# ESP32_Expanded_Board.net
KiCad netlist of a schematic drawn in EasyEDA Pro
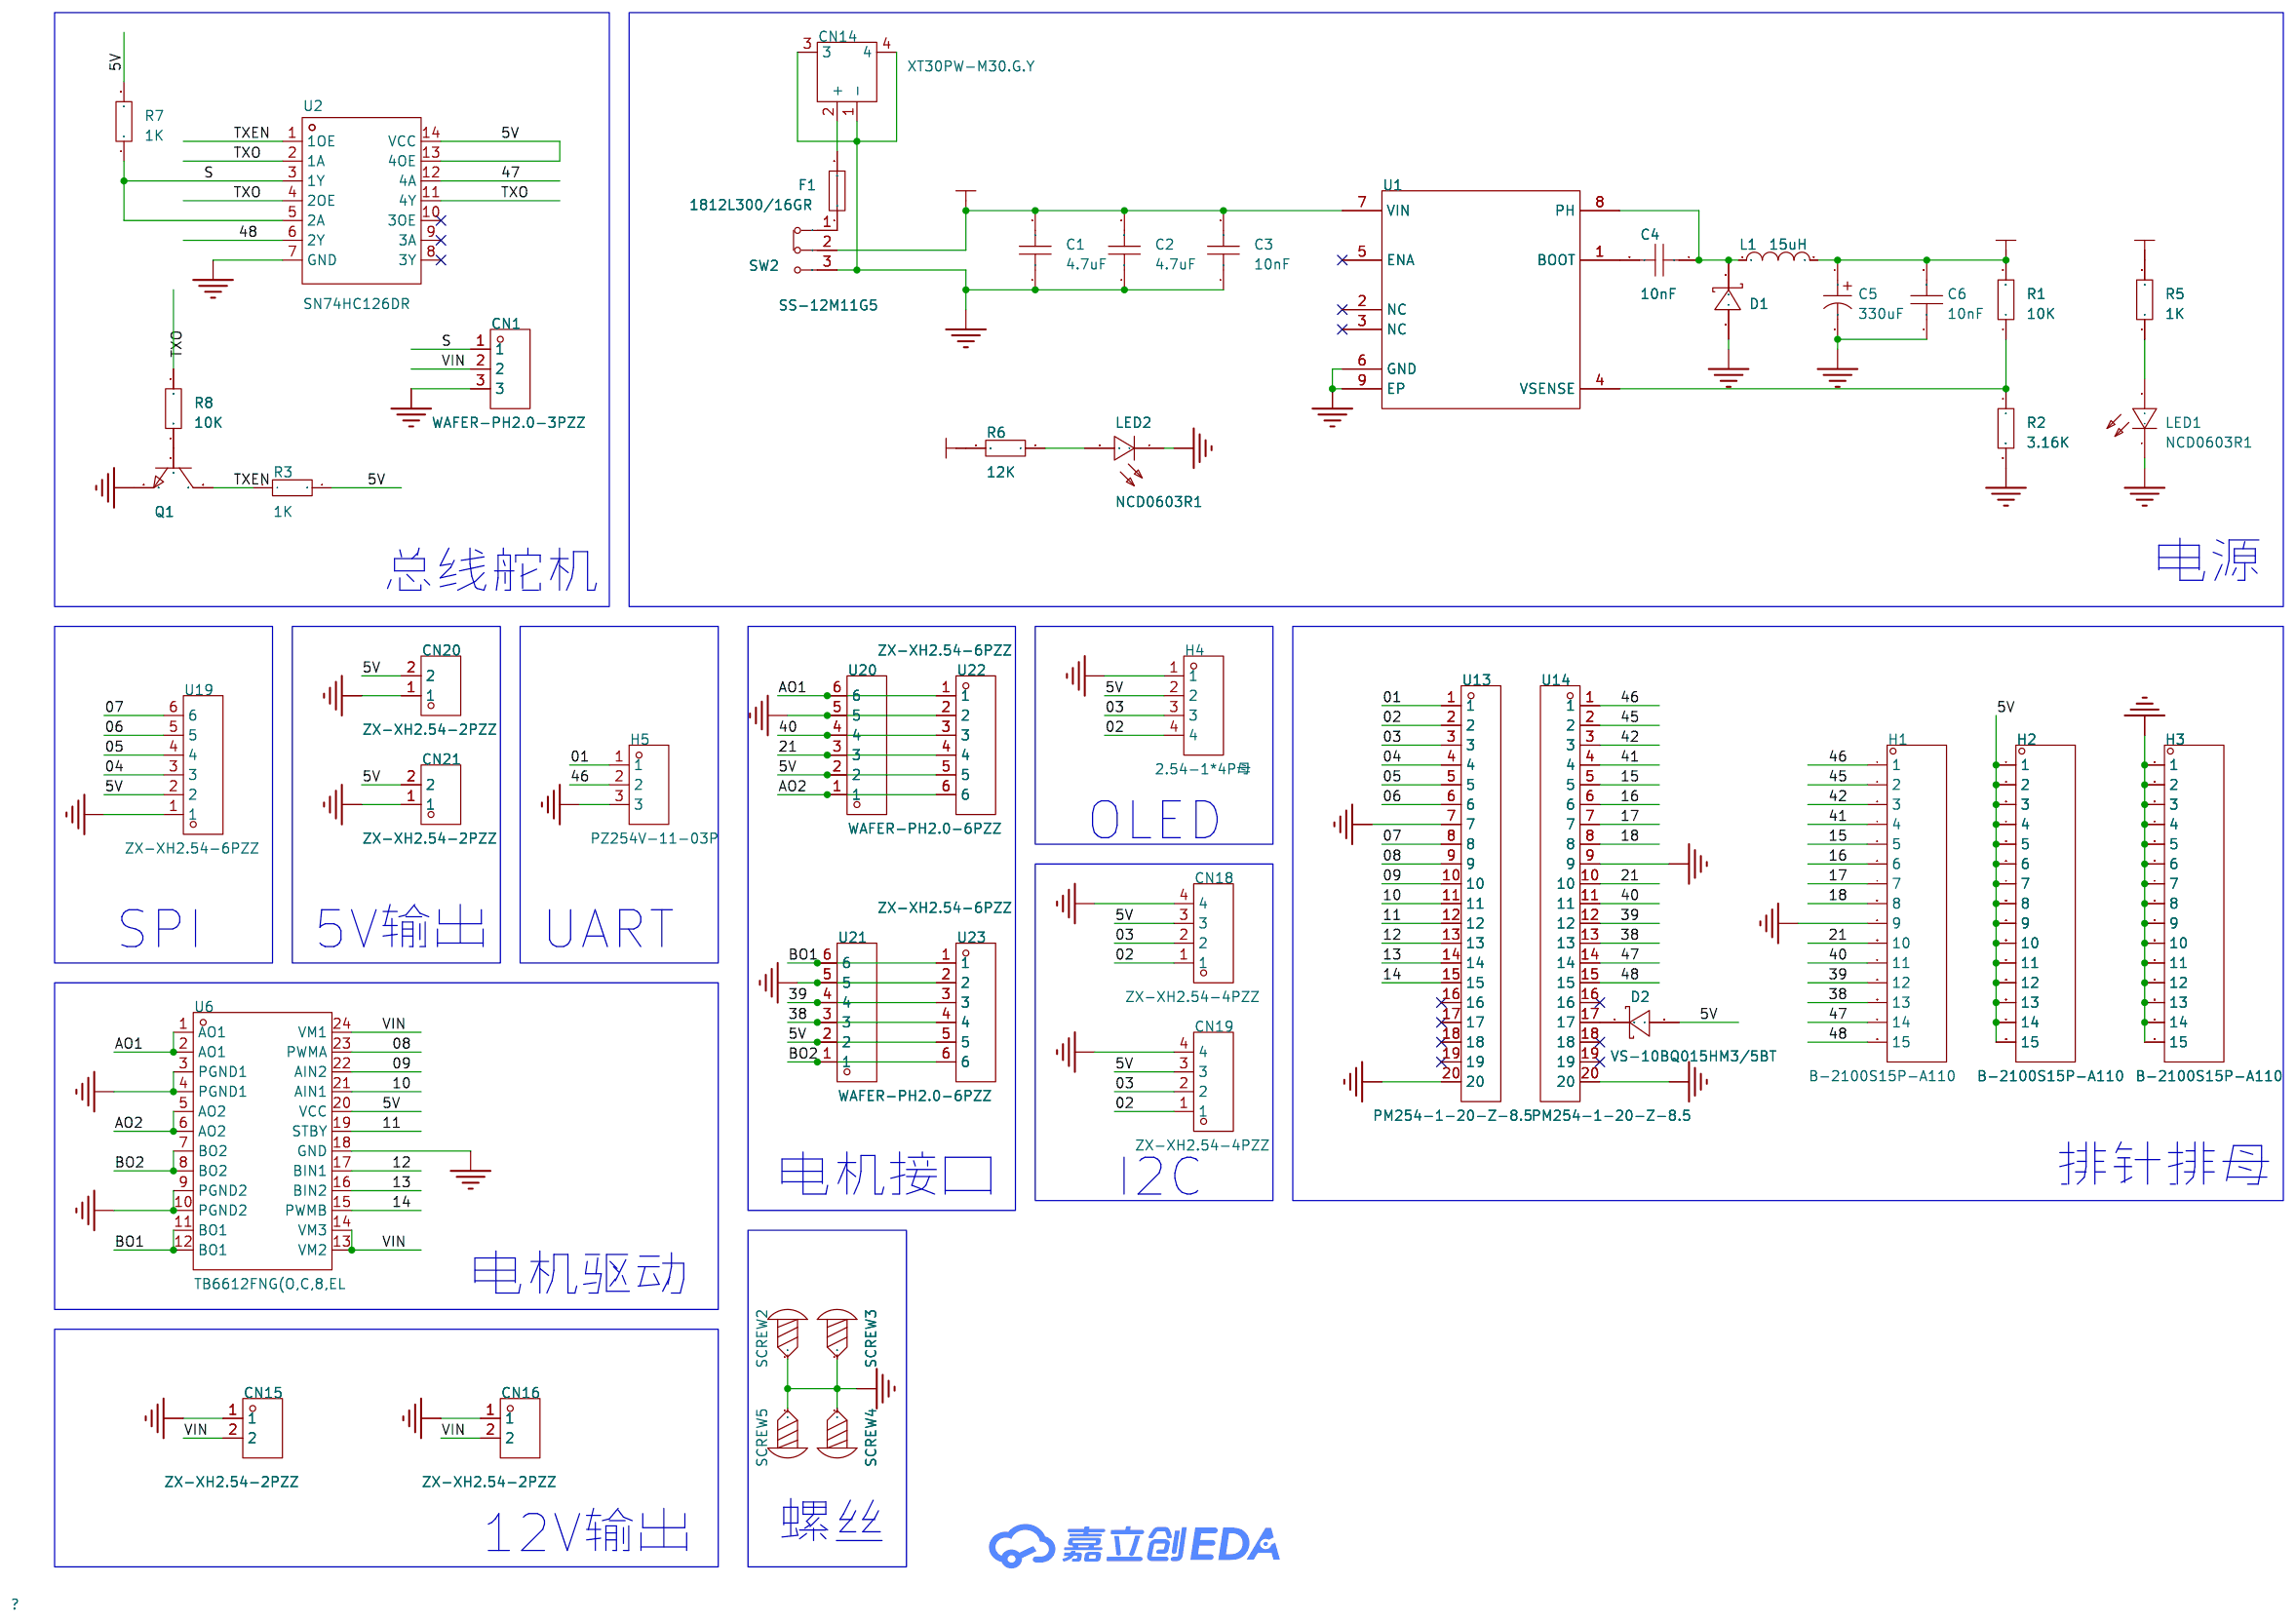
[diagram p0: schematic sheet]

(export (version "E")
  (design (tool "Eeschema 10.0.6"))
  (components
    (comp (ref "C1")
      (value "4.7uF")
      (footprint "easyedapro:C0603")
      (libsource (lib "easyedapro") (part "CapAcitance"))
    )
    (comp (ref "C2")
      (value "4.7uF")
      (footprint "easyedapro:C0603")
      (libsource (lib "easyedapro") (part "CapAcitance"))
    )
    (comp (ref "C3")
      (value "10nF")
      (footprint "easyedapro:C0603")
      (libsource (lib "easyedapro") (part "CapAcitance"))
    )
    (comp (ref "C4")
      (value "10nF")
      (footprint "easyedapro:C0603")
      (libsource (lib "easyedapro") (part "CapAcitance"))
    )
    (comp (ref "C5")
      (value "330uF")
      (footprint "easyedapro:CAP-SMD_BD10.0-L10.3-W10.3-LS11.3-FD-1")
      (description "容值:330uF;精度:±20%;额定电压:50V;纹波电流:170mA@120Hz;等效串联电阻:-;")
      (fields
        (field (name "Manufacturer Part") "RVT330UF50V167RV085")
        (field (name "Manufacturer") "KNSCHA(科尼盛)")
      )
      (libsource (lib "easyedapro") (part "RVT330UF50V167RV085"))
    )
    (comp (ref "C6")
      (value "10nF")
      (footprint "easyedapro:C0603")
      (libsource (lib "easyedapro") (part "CapAcitance"))
    )
    (comp (ref "CN1")
      (value "WAFER-PH2.0-3PZZ")
      (footprint "easyedapro:CONN-TH_PH2.0D-L-3P")
      (description "插针结构:1x3P;间距:2mm;安装方式:直插;参考系列:PH;总PIN数:3P;排数:1;每排PIN数:3;额定电流:2A;工作温度范围:-25°C~+85°C;")
      (fields (field (name "Manufacturer") "XUNPU(讯普)"))
      (libsource (lib "easyedapro") (part "WAFER-PH2.0-3PZZ"))
    )
    (comp (ref "CN14")
      (value "XT30PW-M30.G.Y")
      (footprint "easyedapro:CONN-TH_XT30PW-M")
      (description "类别:-;类型1:-;")
      (fields (field (name "Manufacturer") "AMASS(艾迈斯)"))
      (libsource (lib "easyedapro") (part "XT30PW-M"))
    )
    (comp (ref "CN15")
      (value "ZX-XH2.54-2PZZ")
      (footprint "easyedapro:CONN-TH_2P-P2.50_HX25003-2A")
      (fields (field (name "Manufacturer") "Megastar(兆星)"))
      (libsource (lib "easyedapro") (part "ZX-XH2.54-2PZZ"))
    )
    (comp (ref "CN16")
      (value "ZX-XH2.54-2PZZ")
      (footprint "easyedapro:CONN-TH_2P-P2.50_HX25003-2A")
      (fields (field (name "Manufacturer") "Megastar(兆星)"))
      (libsource (lib "easyedapro") (part "ZX-XH2.54-2PZZ"))
    )
    (comp (ref "CN18")
      (value "ZX-XH2.54-4PZZ")
      (footprint "easyedapro:CONN-TH_4P-P2.50_4PIN")
      (fields (field (name "Manufacturer") "Megastar(兆星)"))
      (libsource (lib "easyedapro") (part "ZX-XH2.54-4PZZ"))
    )
    (comp (ref "CN19")
      (value "ZX-XH2.54-4PZZ")
      (footprint "easyedapro:CONN-TH_4P-P2.50_4PIN")
      (fields (field (name "Manufacturer") "Megastar(兆星)"))
      (libsource (lib "easyedapro") (part "ZX-XH2.54-4PZZ"))
    )
    (comp (ref "CN20")
      (value "ZX-XH2.54-2PZZ")
      (footprint "easyedapro:CONN-TH_2P-P2.50_HX25003-2A")
      (fields (field (name "Manufacturer") "Megastar(兆星)"))
      (libsource (lib "easyedapro") (part "ZX-XH2.54-2PZZ"))
    )
    (comp (ref "CN21")
      (value "ZX-XH2.54-2PZZ")
      (footprint "easyedapro:CONN-TH_2P-P2.50_HX25003-2A")
      (fields (field (name "Manufacturer") "Megastar(兆星)"))
      (libsource (lib "easyedapro") (part "ZX-XH2.54-2PZZ"))
    )
    (comp (ref "D1")
      (value "B540C-13-F")
      (footprint "easyedapro:SMC_L7.1-W6.2-LS8.1-RD")
      (description "正向压降(Vf):550mV@5A;直流反向耐压(Vr):40V;平均整流电流(Io):5A;")
      (fields (field (name "Manufacturer") "DIODES(美台)"))
      (libsource (lib "easyedapro") (part "B540C-13-F"))
    )
    (comp (ref "D2")
      (value "VS-10BQ015HM3/5BT")
      (footprint "easyedapro:SMB_L4.6-W3.6-LS5.3-RD")
      (description "正向压降(Vf):210mV@1A;直流反向耐压(Vr):15V;整流电流:1A;")
      (fields (field (name "Manufacturer") "VISHAY(威世)"))
      (libsource (lib "easyedapro") (part "VS-10BQ015HM3/5BT"))
    )
    (comp (ref "F1")
      (value "1812L300/16GR")
      (footprint "easyedapro:F1812")
      (description "最大电压:16V;最大电流:40A;保持电流:3A;跳闸电流:5A;")
      (fields (field (name "Manufacturer") "LUTE(陆特)"))
      (libsource (lib "easyedapro") (part "1812L300/16GR"))
    )
    (comp (ref "H1")
      (value "B-2100S15P-A110")
      (footprint "easyedapro:HDR-TH_15P-P2.54-V-M")
      (fields (field (name "Manufacturer") "Ckmtw(灿科盟)"))
      (libsource (lib "easyedapro") (part "Header-Male-2.54_1x15"))
    )
    (comp (ref "H2")
      (value "B-2100S15P-A110")
      (footprint "easyedapro:HDR-TH_15P-P2.54-V-M")
      (fields (field (name "Manufacturer") "Ckmtw(灿科盟)"))
      (libsource (lib "easyedapro") (part "Header-Male-2.54_1x15"))
    )
    (comp (ref "H3")
      (value "B-2100S15P-A110")
      (footprint "easyedapro:HDR-TH_15P-P2.54-V-M")
      (fields (field (name "Manufacturer") "Ckmtw(灿科盟)"))
      (libsource (lib "easyedapro") (part "Header-Male-2.54_1x15"))
    )
    (comp (ref "H4")
      (value "2.54-1*4P母")
      (footprint "easyedapro:HDR-TH_4P-P2.54-V-F")
      (fields (field (name "Manufacturer") "BOOMELE(博穆精密)"))
      (libsource (lib "easyedapro") (part "2.54-1*4P母"))
    )
    (comp (ref "H5")
      (value "PZ254V-11-03P")
      (footprint "easyedapro:HDR-TH_3P-P2.54-V-M")
      (fields (field (name "Manufacturer") "XFCN(兴飞)"))
      (libsource (lib "easyedapro") (part "PZ254V-11-03P_C2937625"))
    )
    (comp (ref "L1")
      (value "15uH")
      (footprint "easyedapro:IND-SMD_L11.5-W10.0_FXL1040")
      (description "电感值:15uH;精度:±20%;额定电流:6.5A;饱和电流(Isat):7A;类型:一体成型电感;")
      (fields (field (name "Manufacturer Part") "FXL1040-150-M") (field (name "Manufacturer") "cjiang(长江微电)"))
      (libsource (lib "easyedapro") (part "FXL1040-150-M"))
    )
    (comp (ref "LED1")
      (value "NCD0603R1")
      (footprint "easyedapro:LED0603-RD_RED")
      (fields (field (name "Manufacturer") "国星光电"))
      (libsource (lib "easyedapro") (part "FC-DA1608HRK-620D"))
    )
    (comp (ref "LED2")
      (value "NCD0603R1")
      (footprint "easyedapro:LED0603-RD_RED")
      (fields (field (name "Manufacturer") "国星光电"))
      (libsource (lib "easyedapro") (part "FC-DA1608HRK-620D"))
    )
    (comp (ref "Q1")
      (value "~")
      (footprint "easyedapro:S8050_SOT-23")
      (libsource (lib "easyedapro") (part "NPN"))
    )
    (comp (ref "R1") (value "10K") (footprint "easyedapro:R0603") (libsource (lib "easyedapro") (part "电阻")))
    (comp (ref "R2")
      (value "3.16K")
      (footprint "easyedapro:R0603")
      (libsource (lib "easyedapro") (part "电阻"))
    )
    (comp (ref "R3") (value "1K") (footprint "easyedapro:R0603") (libsource (lib "easyedapro") (part "电阻")))
    (comp (ref "R5") (value "1K") (footprint "easyedapro:R0603") (libsource (lib "easyedapro") (part "电阻")))
    (comp (ref "R6") (value "12K") (footprint "easyedapro:R0603") (libsource (lib "easyedapro") (part "电阻")))
    (comp (ref "R7") (value "1K") (footprint "easyedapro:R0603") (libsource (lib "easyedapro") (part "电阻")))
    (comp (ref "R8") (value "10K") (footprint "easyedapro:R0603") (libsource (lib "easyedapro") (part "电阻")))
    (comp (ref "SCREW2")
      (value "~")
      (footprint "easyedapro:M2螺丝")
      (libsource (lib "easyedapro") (part "螺丝孔"))
    )
    (comp (ref "SCREW3")
      (value "~")
      (footprint "easyedapro:M2螺丝")
      (libsource (lib "easyedapro") (part "螺丝孔"))
    )
    (comp (ref "SCREW4")
      (value "~")
      (footprint "easyedapro:M2螺丝")
      (libsource (lib "easyedapro") (part "螺丝孔"))
    )
    (comp (ref "SCREW5")
      (value "~")
      (footprint "easyedapro:M2螺丝")
      (libsource (lib "easyedapro") (part "螺丝孔"))
    )
    (comp (ref "SW2")
      (value "SS-12M11G5")
      (footprint "easyedapro:SW-TH_XKB_SS-12M11XX")
      (description "电路结构:单刀双掷;安装方式:直插;开关颜色:黑色;额定电流(DC):6A;额定电压(DC):120V;额定电流(AC):6A;额定电压(AC):120V;机械寿命:1万次;")
      (fields (field (name "Manufacturer") "XKB Connectivity(中国星坤)"))
      (libsource (lib "easyedapro") (part "SS-12M11G5"))
    )
    (comp (ref "U1")
      (value "TPS5450DDAR")
      (footprint "easyedapro:SOP-8_L4.9-W3.9-P1.27-LS6.0-BL-EP")
      (description "功能类型:降压型;输出类型:可调;输入电压:5.5V~36V;输出电压:1.221V~31.32V;输出电流(最大值):5A;")
      (fields (field (name "Manufacturer") "TI(德州仪器)"))
      (libsource (lib "easyedapro") (part "TPS5450DDAR"))
    )
    (comp (ref "U2")
      (value "SN74HC126DR")
      (footprint "easyedapro:SOIC-14_L8.7-W3.9-P1.27-LS6.0-BL")
      (description "输入类型:-;电源电压:2V~6V;元件数:4;每个元件位数:1;灌电流(IOL):7.8mA;拉电流(IOH):7.8mA;")
      (fields (field (name "Manufacturer") "TI(德州仪器)"))
      (libsource (lib "easyedapro") (part "SN74HC126DR"))
    )
    (comp (ref "U6")
      (value "TB6612FNG(O,C,8,EL")
      (footprint "easyedapro:SSOP-24_L8.4-W5.8-P0.65-LS7.8-BL")
      (description "双直流电机驱动器集成电路")
      (fields (field (name "Manufacturer") "TOSHIBA(东芝)"))
      (libsource (lib "easyedapro") (part "TB6612FNG(O,C,8,EL"))
    )
    (comp (ref "U13")
      (value "PM254-1-20-Z-8.5")
      (footprint "easyedapro:HDR-TH_20P-P2.54-V-F-2")
      (fields (field (name "Manufacturer") "HCTL(华灿天禄)"))
      (libsource (lib "easyedapro") (part "PM254-1-20-Z-8.5"))
    )
    (comp (ref "U14")
      (value "PM254-1-20-Z-8.5")
      (footprint "easyedapro:HDR-TH_20P-P2.54-V-F-2")
      (fields (field (name "Manufacturer") "HCTL(华灿天禄)"))
      (libsource (lib "easyedapro") (part "PM254-1-20-Z-8.5"))
    )
    (comp (ref "U19")
      (value "ZX-XH2.54-6PZZ")
      (footprint "easyedapro:CONN-TH_6P-P2.50_ZX-XH2.54-6PZZ")
      (fields (field (name "Manufacturer") "Megastar(兆星)"))
      (libsource (lib "easyedapro") (part "ZX-XH2.54-6PZZ"))
    )
    (comp (ref "U20")
      (value "WAFER-PH2.0-6PZZ")
      (footprint "easyedapro:CONN-TH_6P-P2.00_PH2.0-6P")
      (description "插针结构:1x6P;间距:2mm;安装方式:直插;参考系列:PH;总PIN数:6P;排数:1;每排PIN数:6;额定电流:2A;工作温度范围:-25°C~+85°C;")
      (fields (field (name "Manufacturer") "XUNPU(讯普)"))
      (libsource (lib "easyedapro") (part "WAFER-PH2.0-6PZZ"))
    )
    (comp (ref "U21")
      (value "WAFER-PH2.0-6PZZ")
      (footprint "easyedapro:CONN-TH_6P-P2.00_PH2.0-6P")
      (description "插针结构:1x6P;间距:2mm;安装方式:直插;参考系列:PH;总PIN数:6P;排数:1;每排PIN数:6;额定电流:2A;工作温度范围:-25°C~+85°C;")
      (fields (field (name "Manufacturer") "XUNPU(讯普)"))
      (libsource (lib "easyedapro") (part "WAFER-PH2.0-6PZZ"))
    )
    (comp (ref "U22")
      (value "ZX-XH2.54-6PZZ")
      (footprint "easyedapro:CONN-TH_6P-P2.50_ZX-XH2.54-6PZZ")
      (fields (field (name "Manufacturer") "Megastar(兆星)"))
      (libsource (lib "easyedapro") (part "ZX-XH2.54-6PZZ"))
    )
    (comp (ref "U23")
      (value "ZX-XH2.54-6PZZ")
      (footprint "easyedapro:CONN-TH_6P-P2.50_ZX-XH2.54-6PZZ")
      (fields (field (name "Manufacturer") "Megastar(兆星)"))
      (libsource (lib "easyedapro") (part "ZX-XH2.54-6PZZ"))
    )
  )
  (nets
    (net (code "1") (name "/01") (class "Default")
      (node (ref "H5") (pin "1") (pinfunction "1_1") (pintype "unspecified"))
      (node (ref "U13") (pin "1") (pinfunction "1_1") (pintype "unspecified"))
    )
    (net (code "2") (name "/02") (class "Default")
      (node (ref "CN18") (pin "1") (pinfunction "1_1") (pintype "unspecified"))
      (node (ref "CN19") (pin "1") (pinfunction "1_1") (pintype "unspecified"))
      (node (ref "H4") (pin "4") (pinfunction "4_4") (pintype "unspecified"))
      (node (ref "U13") (pin "2") (pinfunction "2_2") (pintype "unspecified"))
    )
    (net (code "3") (name "/03") (class "Default")
      (node (ref "CN18") (pin "2") (pinfunction "2_2") (pintype "unspecified"))
      (node (ref "CN19") (pin "2") (pinfunction "2_2") (pintype "unspecified"))
      (node (ref "H4") (pin "3") (pinfunction "3_3") (pintype "unspecified"))
      (node (ref "U13") (pin "3") (pinfunction "3_3") (pintype "unspecified"))
    )
    (net (code "4") (name "/04") (class "Default")
      (node (ref "U13") (pin "4") (pinfunction "4_4") (pintype "unspecified"))
      (node (ref "U19") (pin "3") (pinfunction "3_3") (pintype "unspecified"))
    )
    (net (code "5") (name "/05") (class "Default")
      (node (ref "U13") (pin "5") (pinfunction "5_5") (pintype "unspecified"))
      (node (ref "U19") (pin "4") (pinfunction "4_4") (pintype "unspecified"))
    )
    (net (code "6") (name "/06") (class "Default")
      (node (ref "U13") (pin "6") (pinfunction "6_6") (pintype "unspecified"))
      (node (ref "U19") (pin "5") (pinfunction "5_5") (pintype "unspecified"))
    )
    (net (code "7") (name "/07") (class "Default")
      (node (ref "U13") (pin "8") (pinfunction "8_8") (pintype "unspecified"))
      (node (ref "U19") (pin "6") (pinfunction "6_6") (pintype "unspecified"))
    )
    (net (code "8") (name "/08") (class "Default")
      (node (ref "U13") (pin "9") (pinfunction "9_9") (pintype "unspecified"))
      (node (ref "U6") (pin "23") (pinfunction "PWMA_23") (pintype "unspecified"))
    )
    (net (code "9") (name "/09") (class "Default")
      (node (ref "U13") (pin "10") (pinfunction "10_10") (pintype "unspecified"))
      (node (ref "U6") (pin "22") (pinfunction "AIN2_22") (pintype "unspecified"))
    )
    (net (code "10") (name "/10") (class "Default")
      (node (ref "U13") (pin "11") (pinfunction "11_11") (pintype "unspecified"))
      (node (ref "U6") (pin "21") (pinfunction "AIN1_21") (pintype "unspecified"))
    )
    (net (code "11") (name "/11") (class "Default")
      (node (ref "U13") (pin "12") (pinfunction "12_12") (pintype "unspecified"))
      (node (ref "U6") (pin "19") (pinfunction "STBY_19") (pintype "unspecified"))
    )
    (net (code "12") (name "/12") (class "Default")
      (node (ref "U13") (pin "13") (pinfunction "13_13") (pintype "unspecified"))
      (node (ref "U6") (pin "17") (pinfunction "BIN1_17") (pintype "unspecified"))
    )
    (net (code "13") (name "/13") (class "Default")
      (node (ref "U13") (pin "14") (pinfunction "14_14") (pintype "unspecified"))
      (node (ref "U6") (pin "16") (pinfunction "BIN2_16") (pintype "unspecified"))
    )
    (net (code "14") (name "/14") (class "Default")
      (node (ref "U13") (pin "15") (pinfunction "15_15") (pintype "unspecified"))
      (node (ref "U6") (pin "15") (pinfunction "PWMB_15") (pintype "unspecified"))
    )
    (net (code "15") (name "/15") (class "Default")
      (node (ref "H1") (pin "5") (pinfunction "5_5") (pintype "unspecified"))
      (node (ref "U14") (pin "5") (pinfunction "5_5") (pintype "unspecified"))
    )
    (net (code "16") (name "/16") (class "Default")
      (node (ref "H1") (pin "6") (pinfunction "6_6") (pintype "unspecified"))
      (node (ref "U14") (pin "6") (pinfunction "6_6") (pintype "unspecified"))
    )
    (net (code "17") (name "/17") (class "Default")
      (node (ref "H1") (pin "7") (pinfunction "7_7") (pintype "unspecified"))
      (node (ref "U14") (pin "7") (pinfunction "7_7") (pintype "unspecified"))
    )
    (net (code "18") (name "/18") (class "Default")
      (node (ref "H1") (pin "8") (pinfunction "8_8") (pintype "unspecified"))
      (node (ref "U14") (pin "8") (pinfunction "8_8") (pintype "unspecified"))
    )
    (net (code "19") (name "/21") (class "Default")
      (node (ref "H1") (pin "10") (pinfunction "10_10") (pintype "unspecified"))
      (node (ref "U14") (pin "10") (pinfunction "10_10") (pintype "unspecified"))
      (node (ref "U20") (pin "3") (pinfunction "3_3") (pintype "unspecified"))
      (node (ref "U22") (pin "4") (pinfunction "4_4") (pintype "unspecified"))
    )
    (net (code "20") (name "/38") (class "Default")
      (node (ref "H1") (pin "13") (pinfunction "13_13") (pintype "unspecified"))
      (node (ref "U14") (pin "13") (pinfunction "13_13") (pintype "unspecified"))
      (node (ref "U21") (pin "3") (pinfunction "3_3") (pintype "unspecified"))
      (node (ref "U23") (pin "4") (pinfunction "4_4") (pintype "unspecified"))
    )
    (net (code "21") (name "/39") (class "Default")
      (node (ref "H1") (pin "12") (pinfunction "12_12") (pintype "unspecified"))
      (node (ref "U14") (pin "12") (pinfunction "12_12") (pintype "unspecified"))
      (node (ref "U21") (pin "4") (pinfunction "4_4") (pintype "unspecified"))
      (node (ref "U23") (pin "3") (pinfunction "3_3") (pintype "unspecified"))
    )
    (net (code "22") (name "/40") (class "Default")
      (node (ref "H1") (pin "11") (pinfunction "11_11") (pintype "unspecified"))
      (node (ref "U14") (pin "11") (pinfunction "11_11") (pintype "unspecified"))
      (node (ref "U20") (pin "4") (pinfunction "4_4") (pintype "unspecified"))
      (node (ref "U22") (pin "3") (pinfunction "3_3") (pintype "unspecified"))
    )
    (net (code "23") (name "/41") (class "Default")
      (node (ref "H1") (pin "4") (pinfunction "4_4") (pintype "unspecified"))
      (node (ref "U14") (pin "4") (pinfunction "4_4") (pintype "unspecified"))
    )
    (net (code "24") (name "/42") (class "Default")
      (node (ref "H1") (pin "3") (pinfunction "3_3") (pintype "unspecified"))
      (node (ref "U14") (pin "3") (pinfunction "3_3") (pintype "unspecified"))
    )
    (net (code "25") (name "/45") (class "Default")
      (node (ref "H1") (pin "2") (pinfunction "2_2") (pintype "unspecified"))
      (node (ref "U14") (pin "2") (pinfunction "2_2") (pintype "unspecified"))
    )
    (net (code "26") (name "/46") (class "Default")
      (node (ref "H1") (pin "1") (pinfunction "1_1") (pintype "unspecified"))
      (node (ref "H5") (pin "2") (pinfunction "2_2") (pintype "unspecified"))
      (node (ref "U14") (pin "1") (pinfunction "1_1") (pintype "unspecified"))
    )
    (net (code "27") (name "/47") (class "Default")
      (node (ref "H1") (pin "14") (pinfunction "14_14") (pintype "unspecified"))
      (node (ref "U14") (pin "14") (pinfunction "14_14") (pintype "unspecified"))
      (node (ref "U2") (pin "12") (pinfunction "4A_12") (pintype "input"))
    )
    (net (code "28") (name "/48") (class "Default")
      (node (ref "H1") (pin "15") (pinfunction "15_15") (pintype "unspecified"))
      (node (ref "U14") (pin "15") (pinfunction "15_15") (pintype "unspecified"))
      (node (ref "U2") (pin "6") (pinfunction "2Y_6") (pintype "input"))
    )
    (net (code "29") (name "/AO1") (class "Default")
      (node (ref "U20") (pin "6") (pinfunction "6_6") (pintype "unspecified"))
      (node (ref "U22") (pin "1") (pinfunction "1_1") (pintype "unspecified"))
      (node (ref "U6") (pin "1") (pinfunction "AO1_1") (pintype "unspecified"))
      (node (ref "U6") (pin "2") (pinfunction "AO1_2") (pintype "unspecified"))
    )
    (net (code "30") (name "/AO2") (class "Default")
      (node (ref "U20") (pin "1") (pinfunction "1_1") (pintype "unspecified"))
      (node (ref "U22") (pin "6") (pinfunction "6_6") (pintype "unspecified"))
      (node (ref "U6") (pin "5") (pinfunction "AO2_5") (pintype "unspecified"))
      (node (ref "U6") (pin "6") (pinfunction "AO2_6") (pintype "unspecified"))
    )
    (net (code "31") (name "/BO1") (class "Default")
      (node (ref "U21") (pin "6") (pinfunction "6_6") (pintype "unspecified"))
      (node (ref "U23") (pin "1") (pinfunction "1_1") (pintype "unspecified"))
      (node (ref "U6") (pin "11") (pinfunction "BO1_11") (pintype "unspecified"))
      (node (ref "U6") (pin "12") (pinfunction "BO1_12") (pintype "unspecified"))
    )
    (net (code "32") (name "/BO2") (class "Default")
      (node (ref "U21") (pin "1") (pinfunction "1_1") (pintype "unspecified"))
      (node (ref "U23") (pin "6") (pinfunction "6_6") (pintype "unspecified"))
      (node (ref "U6") (pin "7") (pinfunction "BO2_7") (pintype "unspecified"))
      (node (ref "U6") (pin "8") (pinfunction "BO2_8") (pintype "unspecified"))
    )
    (net (code "33") (name "/S") (class "Default")
      (node (ref "CN1") (pin "1") (pinfunction "1_1") (pintype "unspecified"))
      (node (ref "R7") (pin "1") (pinfunction "1_1") (pintype "input"))
      (node (ref "U2") (pin "3") (pinfunction "1Y_3") (pintype "input"))
      (node (ref "U2") (pin "5") (pinfunction "2A_5") (pintype "input"))
    )
    (net (code "34") (name "/TXEN") (class "Default")
      (node (ref "Q1") (pin "3") (pinfunction "3_3") (pintype "unspecified"))
      (node (ref "R3") (pin "1") (pinfunction "1_1") (pintype "input"))
      (node (ref "U2") (pin "1") (pinfunction "1OE_1") (pintype "input"))
    )
    (net (code "35") (name "/TXO") (class "Default")
      (node (ref "R8") (pin "1") (pinfunction "1_1") (pintype "input"))
      (node (ref "U2") (pin "11") (pinfunction "4Y_11") (pintype "input"))
      (node (ref "U2") (pin "2") (pinfunction "1A_2") (pintype "input"))
      (node (ref "U2") (pin "4") (pinfunction "2OE_4") (pintype "input"))
    )
    (net (code "36") (name "5V") (class "Default")
      (node (ref "C5") (pin "1") (pinfunction "1_1") (pintype "input"))
      (node (ref "C6") (pin "2") (pinfunction "2_2") (pintype "input"))
      (node (ref "CN18") (pin "3") (pinfunction "3_3") (pintype "unspecified"))
      (node (ref "CN19") (pin "3") (pinfunction "3_3") (pintype "unspecified"))
      (node (ref "CN20") (pin "2") (pinfunction "2_2") (pintype "unspecified"))
      (node (ref "CN21") (pin "2") (pinfunction "2_2") (pintype "unspecified"))
      (node (ref "D2") (pin "2") (pinfunction "A_2") (pintype "unspecified"))
      (node (ref "H2") (pin "1") (pinfunction "1_1") (pintype "unspecified"))
      (node (ref "H2") (pin "10") (pinfunction "10_10") (pintype "unspecified"))
      (node (ref "H2") (pin "11") (pinfunction "11_11") (pintype "unspecified"))
      (node (ref "H2") (pin "12") (pinfunction "12_12") (pintype "unspecified"))
      (node (ref "H2") (pin "13") (pinfunction "13_13") (pintype "unspecified"))
      (node (ref "H2") (pin "14") (pinfunction "14_14") (pintype "unspecified"))
      (node (ref "H2") (pin "15") (pinfunction "15_15") (pintype "unspecified"))
      (node (ref "H2") (pin "2") (pinfunction "2_2") (pintype "unspecified"))
      (node (ref "H2") (pin "3") (pinfunction "3_3") (pintype "unspecified"))
      (node (ref "H2") (pin "4") (pinfunction "4_4") (pintype "unspecified"))
      (node (ref "H2") (pin "5") (pinfunction "5_5") (pintype "unspecified"))
      (node (ref "H2") (pin "6") (pinfunction "6_6") (pintype "unspecified"))
      (node (ref "H2") (pin "7") (pinfunction "7_7") (pintype "unspecified"))
      (node (ref "H2") (pin "8") (pinfunction "8_8") (pintype "unspecified"))
      (node (ref "H2") (pin "9") (pinfunction "9_9") (pintype "unspecified"))
      (node (ref "H4") (pin "2") (pinfunction "2_2") (pintype "unspecified"))
      (node (ref "L1") (pin "2") (pinfunction "2_2") (pintype "unspecified"))
      (node (ref "R1") (pin "2") (pinfunction "2_2") (pintype "input"))
      (node (ref "R3") (pin "2") (pinfunction "2_2") (pintype "input"))
      (node (ref "R5") (pin "2") (pinfunction "2_2") (pintype "input"))
      (node (ref "R7") (pin "2") (pinfunction "2_2") (pintype "input"))
      (node (ref "U19") (pin "2") (pinfunction "2_2") (pintype "unspecified"))
      (node (ref "U2") (pin "13") (pinfunction "4OE_13") (pintype "input"))
      (node (ref "U2") (pin "14") (pinfunction "VCC_14") (pintype "input"))
      (node (ref "U20") (pin "2") (pinfunction "2_2") (pintype "unspecified"))
      (node (ref "U21") (pin "2") (pinfunction "2_2") (pintype "unspecified"))
      (node (ref "U22") (pin "5") (pinfunction "5_5") (pintype "unspecified"))
      (node (ref "U23") (pin "5") (pinfunction "5_5") (pintype "unspecified"))
      (node (ref "U6") (pin "20") (pinfunction "VCC_20") (pintype "unspecified"))
    )
    (net (code "37") (name "GND") (class "Default")
      (node (ref "C1") (pin "1") (pinfunction "1_1") (pintype "input"))
      (node (ref "C2") (pin "1") (pinfunction "1_1") (pintype "input"))
      (node (ref "C3") (pin "1") (pinfunction "1_1") (pintype "input"))
      (node (ref "C5") (pin "2") (pinfunction "2_2") (pintype "input"))
      (node (ref "C6") (pin "1") (pinfunction "1_1") (pintype "input"))
      (node (ref "CN1") (pin "3") (pinfunction "3_3") (pintype "unspecified"))
      (node (ref "CN14") (pin "1") (pinfunction "-_1") (pintype "unspecified"))
      (node (ref "CN14") (pin "3") (pinfunction "3_3") (pintype "unspecified"))
      (node (ref "CN14") (pin "4") (pinfunction "4_4") (pintype "unspecified"))
      (node (ref "CN15") (pin "1") (pinfunction "1_1") (pintype "unspecified"))
      (node (ref "CN16") (pin "1") (pinfunction "1_1") (pintype "unspecified"))
      (node (ref "CN18") (pin "4") (pinfunction "4_4") (pintype "unspecified"))
      (node (ref "CN19") (pin "4") (pinfunction "4_4") (pintype "unspecified"))
      (node (ref "CN20") (pin "1") (pinfunction "1_1") (pintype "unspecified"))
      (node (ref "CN21") (pin "1") (pinfunction "1_1") (pintype "unspecified"))
      (node (ref "D1") (pin "2") (pinfunction "A_2") (pintype "unspecified"))
      (node (ref "H1") (pin "9") (pinfunction "9_9") (pintype "unspecified"))
      (node (ref "H3") (pin "1") (pinfunction "1_1") (pintype "unspecified"))
      (node (ref "H3") (pin "10") (pinfunction "10_10") (pintype "unspecified"))
      (node (ref "H3") (pin "11") (pinfunction "11_11") (pintype "unspecified"))
      (node (ref "H3") (pin "12") (pinfunction "12_12") (pintype "unspecified"))
      (node (ref "H3") (pin "13") (pinfunction "13_13") (pintype "unspecified"))
      (node (ref "H3") (pin "14") (pinfunction "14_14") (pintype "unspecified"))
      (node (ref "H3") (pin "15") (pinfunction "15_15") (pintype "unspecified"))
      (node (ref "H3") (pin "2") (pinfunction "2_2") (pintype "unspecified"))
      (node (ref "H3") (pin "3") (pinfunction "3_3") (pintype "unspecified"))
      (node (ref "H3") (pin "4") (pinfunction "4_4") (pintype "unspecified"))
      (node (ref "H3") (pin "5") (pinfunction "5_5") (pintype "unspecified"))
      (node (ref "H3") (pin "6") (pinfunction "6_6") (pintype "unspecified"))
      (node (ref "H3") (pin "7") (pinfunction "7_7") (pintype "unspecified"))
      (node (ref "H3") (pin "8") (pinfunction "8_8") (pintype "unspecified"))
      (node (ref "H3") (pin "9") (pinfunction "9_9") (pintype "unspecified"))
      (node (ref "H4") (pin "1") (pinfunction "1_1") (pintype "unspecified"))
      (node (ref "H5") (pin "3") (pinfunction "3_3") (pintype "unspecified"))
      (node (ref "LED1") (pin "1") (pinfunction "K_1") (pintype "input"))
      (node (ref "LED2") (pin "1") (pinfunction "K_1") (pintype "input"))
      (node (ref "Q1") (pin "2") (pinfunction "2_2") (pintype "unspecified"))
      (node (ref "R2") (pin "2") (pinfunction "2_2") (pintype "input"))
      (node (ref "SCREW2") (pin "1") (pinfunction "1_1") (pintype "input"))
      (node (ref "SCREW3") (pin "1") (pinfunction "1_1") (pintype "input"))
      (node (ref "SCREW4") (pin "1") (pinfunction "1_1") (pintype "input"))
      (node (ref "SCREW5") (pin "1") (pinfunction "1_1") (pintype "input"))
      (node (ref "SW2") (pin "3") (pinfunction "3_3") (pintype "unspecified"))
      (node (ref "U1") (pin "6") (pinfunction "GND_6") (pintype "unspecified"))
      (node (ref "U1") (pin "9") (pinfunction "EP_9") (pintype "unspecified"))
      (node (ref "U13") (pin "20") (pinfunction "20_20") (pintype "unspecified"))
      (node (ref "U13") (pin "7") (pinfunction "7_7") (pintype "unspecified"))
      (node (ref "U14") (pin "20") (pinfunction "20_20") (pintype "unspecified"))
      (node (ref "U14") (pin "9") (pinfunction "9_9") (pintype "unspecified"))
      (node (ref "U19") (pin "1") (pinfunction "1_1") (pintype "unspecified"))
      (node (ref "U2") (pin "7") (pinfunction "GND_7") (pintype "input"))
      (node (ref "U20") (pin "5") (pinfunction "5_5") (pintype "unspecified"))
      (node (ref "U21") (pin "5") (pinfunction "5_5") (pintype "unspecified"))
      (node (ref "U22") (pin "2") (pinfunction "2_2") (pintype "unspecified"))
      (node (ref "U23") (pin "2") (pinfunction "2_2") (pintype "unspecified"))
      (node (ref "U6") (pin "10") (pinfunction "PGND2_10") (pintype "unspecified"))
      (node (ref "U6") (pin "18") (pinfunction "GND_18") (pintype "unspecified"))
      (node (ref "U6") (pin "3") (pinfunction "PGND1_3") (pintype "unspecified"))
      (node (ref "U6") (pin "4") (pinfunction "PGND1_4") (pintype "unspecified"))
      (node (ref "U6") (pin "9") (pinfunction "PGND2_9") (pintype "unspecified"))
    )
    (net (code "38") (name "Net-(CN14-+)") (class "Default")
      (node (ref "CN14") (pin "2") (pinfunction "+_2") (pintype "unspecified"))
      (node (ref "F1") (pin "2") (pinfunction "2_2") (pintype "unspecified"))
    )
    (net (code "39") (name "Net-(D1-K)") (class "Default")
      (node (ref "C4") (pin "1") (pinfunction "1_1") (pintype "input"))
      (node (ref "D1") (pin "1") (pinfunction "K_1") (pintype "unspecified"))
      (node (ref "L1") (pin "1") (pinfunction "1_1") (pintype "unspecified"))
      (node (ref "U1") (pin "8") (pinfunction "PH_8") (pintype "output"))
    )
    (net (code "40") (name "Net-(D2-C)") (class "Default")
      (node (ref "D2") (pin "1") (pinfunction "C_1") (pintype "unspecified"))
      (node (ref "U14") (pin "17") (pinfunction "17_17") (pintype "unspecified"))
    )
    (net (code "41") (name "Net-(F1-Pad1)") (class "Default")
      (node (ref "F1") (pin "1") (pinfunction "1_1") (pintype "unspecified"))
      (node (ref "SW2") (pin "1") (pinfunction "1_1") (pintype "unspecified"))
    )
    (net (code "42") (name "Net-(LED1-A)") (class "Default")
      (node (ref "LED1") (pin "2") (pinfunction "A_2") (pintype "input"))
      (node (ref "R5") (pin "1") (pinfunction "1_1") (pintype "input"))
    )
    (net (code "43") (name "Net-(LED2-A)") (class "Default")
      (node (ref "LED2") (pin "2") (pinfunction "A_2") (pintype "input"))
      (node (ref "R6") (pin "1") (pinfunction "1_1") (pintype "input"))
    )
    (net (code "44") (name "Net-(Q1-Pad1)") (class "Default")
      (node (ref "Q1") (pin "1") (pinfunction "1_1") (pintype "unspecified"))
      (node (ref "R8") (pin "2") (pinfunction "2_2") (pintype "input"))
    )
    (net (code "45") (name "Net-(U1-BOOT)") (class "Default")
      (node (ref "C4") (pin "2") (pinfunction "2_2") (pintype "input"))
      (node (ref "U1") (pin "1") (pinfunction "BOOT_1") (pintype "unspecified"))
    )
    (net (code "46") (name "Net-(U1-VSENSE)") (class "Default")
      (node (ref "R1") (pin "1") (pinfunction "1_1") (pintype "input"))
      (node (ref "R2") (pin "1") (pinfunction "1_1") (pintype "input"))
      (node (ref "U1") (pin "4") (pinfunction "VSENSE_4") (pintype "output"))
    )
    (net (code "47") (name "VIN") (class "Default")
      (node (ref "C1") (pin "2") (pinfunction "2_2") (pintype "input"))
      (node (ref "C2") (pin "2") (pinfunction "2_2") (pintype "input"))
      (node (ref "C3") (pin "2") (pinfunction "2_2") (pintype "input"))
      (node (ref "CN1") (pin "2") (pinfunction "2_2") (pintype "unspecified"))
      (node (ref "CN15") (pin "2") (pinfunction "2_2") (pintype "unspecified"))
      (node (ref "CN16") (pin "2") (pinfunction "2_2") (pintype "unspecified"))
      (node (ref "R6") (pin "2") (pinfunction "2_2") (pintype "input"))
      (node (ref "SW2") (pin "2") (pinfunction "2_2") (pintype "unspecified"))
      (node (ref "U1") (pin "7") (pinfunction "VIN_7") (pintype "input"))
      (node (ref "U6") (pin "13") (pinfunction "VM2_13") (pintype "unspecified"))
      (node (ref "U6") (pin "14") (pinfunction "VM3_14") (pintype "unspecified"))
      (node (ref "U6") (pin "24") (pinfunction "VM1_24") (pintype "unspecified"))
    )
    (net (code "48") (name "unconnected-(U1-ENA-Pad5)") (class "Default")
      (node (ref "U1") (pin "5") (pinfunction "ENA_5") (pintype "input+no_connect"))
    )
    (net (code "49") (name "unconnected-(U1-NC-Pad2)") (class "Default")
      (node (ref "U1") (pin "2") (pinfunction "NC_2") (pintype "unspecified+no_connect"))
    )
    (net (code "50") (name "unconnected-(U1-NC-Pad3)") (class "Default")
      (node (ref "U1") (pin "3") (pinfunction "NC_3") (pintype "unspecified+no_connect"))
    )
    (net (code "51") (name "unconnected-(U2-3A-Pad9)") (class "Default")
      (node (ref "U2") (pin "9") (pinfunction "3A_9") (pintype "input+no_connect"))
    )
    (net (code "52") (name "unconnected-(U2-3OE-Pad10)") (class "Default")
      (node (ref "U2") (pin "10") (pinfunction "3OE_10") (pintype "input+no_connect"))
    )
    (net (code "53") (name "unconnected-(U2-3Y-Pad8)") (class "Default")
      (node (ref "U2") (pin "8") (pinfunction "3Y_8") (pintype "input+no_connect"))
    )
    (net (code "54") (name "unconnected-(U13-Pad16)") (class "Default")
      (node (ref "U13") (pin "16") (pinfunction "16_16") (pintype "unspecified+no_connect"))
    )
    (net (code "55") (name "unconnected-(U13-Pad17)") (class "Default")
      (node (ref "U13") (pin "17") (pinfunction "17_17") (pintype "unspecified+no_connect"))
    )
    (net (code "56") (name "unconnected-(U13-Pad18)") (class "Default")
      (node (ref "U13") (pin "18") (pinfunction "18_18") (pintype "unspecified+no_connect"))
    )
    (net (code "57") (name "unconnected-(U13-Pad19)") (class "Default")
      (node (ref "U13") (pin "19") (pinfunction "19_19") (pintype "unspecified+no_connect"))
    )
    (net (code "58") (name "unconnected-(U14-Pad16)") (class "Default")
      (node (ref "U14") (pin "16") (pinfunction "16_16") (pintype "unspecified+no_connect"))
    )
    (net (code "59") (name "unconnected-(U14-Pad18)") (class "Default")
      (node (ref "U14") (pin "18") (pinfunction "18_18") (pintype "unspecified+no_connect"))
    )
    (net (code "60") (name "unconnected-(U14-Pad19)") (class "Default")
      (node (ref "U14") (pin "19") (pinfunction "19_19") (pintype "unspecified+no_connect"))
    )
  )
)
